# LAN.net
KiCad netlist of a schematic drawn in Altium Designer
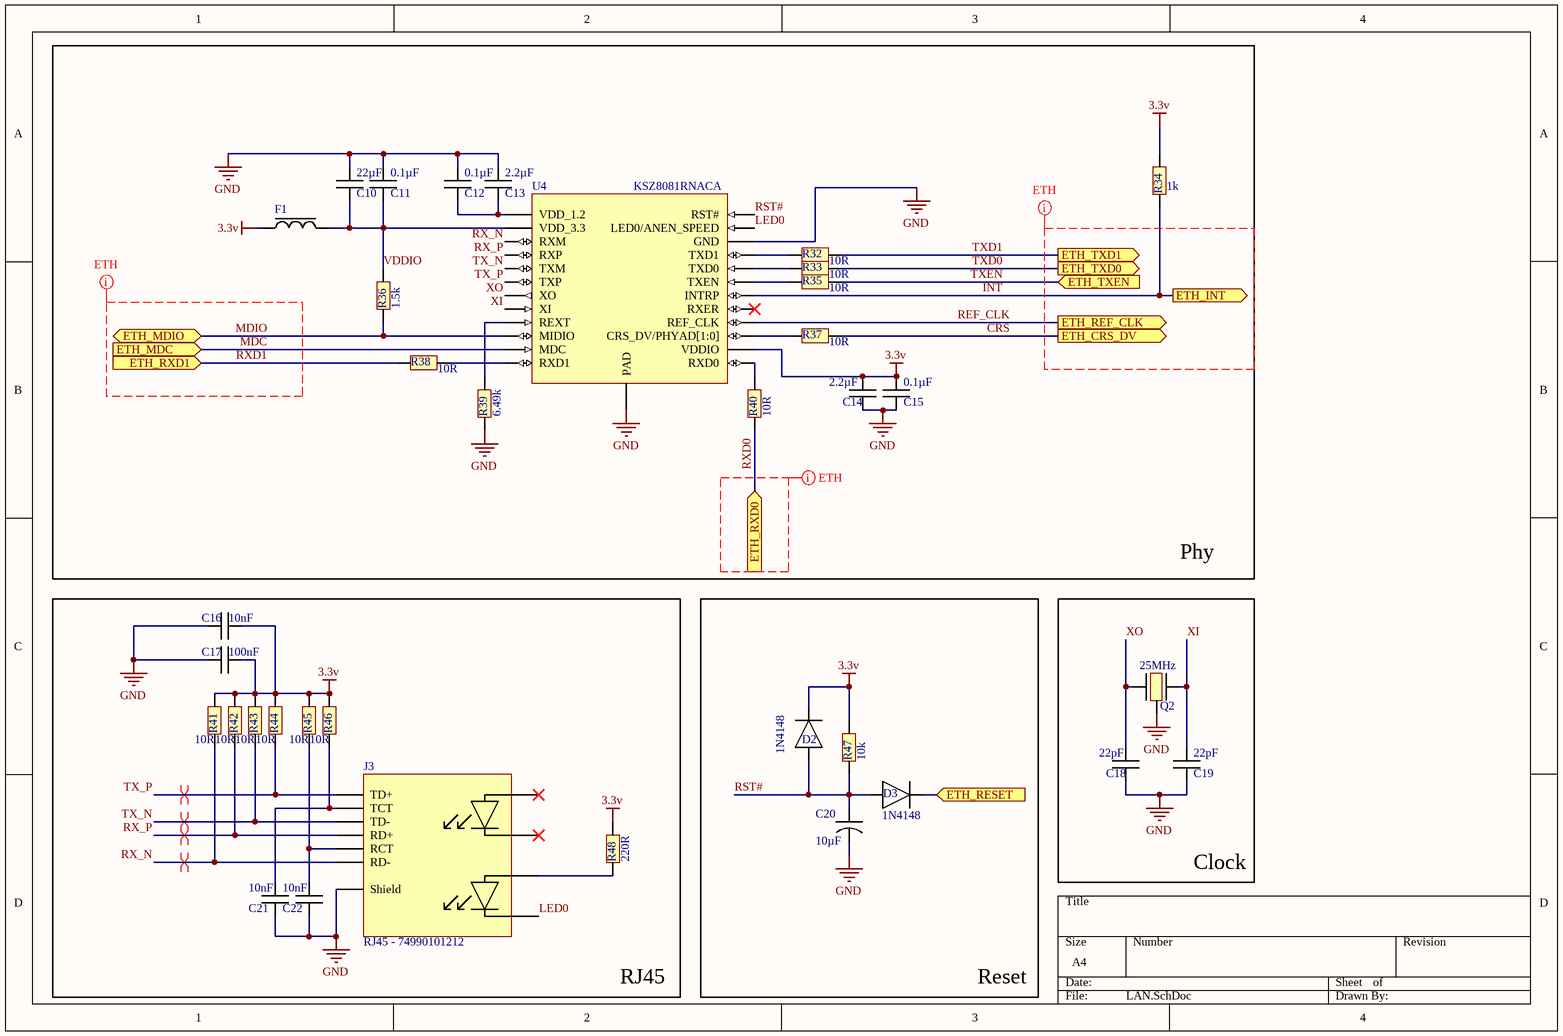
[diagram p0: LAN.SchDoc]

(export (version "E")
  (design (tool "Eeschema 10.0.6"))
  (components
    (comp (ref "C10") (value "22µF") (footprint "0603") (libsource (lib "Carte_design_SCHLib") (part "Capa")))
    (comp (ref "C11")
      (value "0.1µF")
      (footprint "0603")
      (libsource (lib "Carte_design_SCHLib") (part "Capa"))
    )
    (comp (ref "C12")
      (value "0.1µF")
      (footprint "0603")
      (libsource (lib "Carte_design_SCHLib") (part "Capa"))
    )
    (comp (ref "C13")
      (value "2.2µF")
      (footprint "0603")
      (libsource (lib "Carte_design_SCHLib") (part "Capa"))
    )
    (comp (ref "C14")
      (value "2.2µF")
      (footprint "0603")
      (libsource (lib "Carte_design_SCHLib") (part "Capa"))
    )
    (comp (ref "C15")
      (value "0.1µF")
      (footprint "0603")
      (libsource (lib "Carte_design_SCHLib") (part "Capa"))
    )
    (comp (ref "C16") (value "10nF") (footprint "0603") (libsource (lib "Carte_design_SCHLib") (part "Capa")))
    (comp (ref "C17")
      (value "100nF")
      (footprint "0603")
      (libsource (lib "Carte_design_SCHLib") (part "Capa"))
    )
    (comp (ref "C18") (value "22pF") (footprint "0603") (libsource (lib "Carte_design_SCHLib") (part "Capa")))
    (comp (ref "C19") (value "22pF") (footprint "0603") (libsource (lib "Carte_design_SCHLib") (part "Capa")))
    (comp (ref "C20")
      (value "10µF")
      (footprint "Capa_Radial_D4mm_H5.5mm")
      (fields (field (name "TOLERANCE") "20%"))
      (libsource (lib "Carte_design_SCHLib") (part "Capa_pola"))
    )
    (comp (ref "C21") (value "10nF") (footprint "0603") (libsource (lib "Carte_design_SCHLib") (part "Capa")))
    (comp (ref "C22") (value "10nF") (footprint "0603") (libsource (lib "Carte_design_SCHLib") (part "Capa")))
    (comp (ref "D2")
      (value "1N4148")
      (footprint "SOD123")
      (fields (field (name "VOLTAGE") "100V"))
      (libsource (lib "Carte_design_SCHLib") (part "1N4148"))
    )
    (comp (ref "D3")
      (value "1N4148")
      (footprint "SOD123")
      (fields (field (name "VOLTAGE") "100V"))
      (libsource (lib "Carte_design_SCHLib") (part "1N4148"))
    )
    (comp (ref "F1")
      (value "Ferrite")
      (footprint "0805_W1.25")
      (fields (field (name "TOLERANCE") "25%"))
      (libsource (lib "Carte_design_SCHLib") (part "Ferrite"))
    )
    (comp (ref "J3")
      (value "RJ45 - 74990101212")
      (footprint "RJ45")
      (libsource (lib "Carte_design_SCHLib") (part "RJ45"))
    )
    (comp (ref "Q2")
      (value "25MHz")
      (footprint "SMD_3225")
      (libsource (lib "Carte_design_SCHLib") (part "Quartz_25MHz"))
    )
    (comp (ref "R32") (value "10R") (footprint "0603") (libsource (lib "") (part "Resistance_1")))
    (comp (ref "R33") (value "10R") (footprint "0603") (libsource (lib "") (part "Resistance_1")))
    (comp (ref "R34")
      (value "1k")
      (footprint "0603")
      (libsource (lib "Carte_design_SCHLib") (part "Resistance"))
    )
    (comp (ref "R35") (value "10R") (footprint "0603") (libsource (lib "") (part "Resistance_1")))
    (comp (ref "R36") (value "1.5k") (footprint "0603") (libsource (lib "") (part "Resistance_2")))
    (comp (ref "R37") (value "10R") (footprint "0603") (libsource (lib "") (part "Resistance_1")))
    (comp (ref "R38") (value "10R") (footprint "0603") (libsource (lib "") (part "Resistance_3")))
    (comp (ref "R39") (value "6.49k") (footprint "0603") (libsource (lib "") (part "Resistance_2")))
    (comp (ref "R40")
      (value "10R")
      (footprint "0603")
      (libsource (lib "Carte_design_SCHLib") (part "Resistance"))
    )
    (comp (ref "R41") (value "10R") (footprint "0603") (libsource (lib "") (part "Resistance_2")))
    (comp (ref "R42") (value "10R") (footprint "0603") (libsource (lib "") (part "Resistance_2")))
    (comp (ref "R43") (value "10R") (footprint "0603") (libsource (lib "") (part "Resistance_2")))
    (comp (ref "R44") (value "10R") (footprint "0603") (libsource (lib "") (part "Resistance_2")))
    (comp (ref "R45") (value "10R") (footprint "0603") (libsource (lib "") (part "Resistance_2")))
    (comp (ref "R46") (value "10R") (footprint "0603") (libsource (lib "") (part "Resistance_2")))
    (comp (ref "R47") (value "10k") (footprint "0603") (libsource (lib "") (part "Resistance_2")))
    (comp (ref "R48") (value "220R") (footprint "0603") (libsource (lib "") (part "Resistance_2")))
    (comp (ref "U4")
      (value "KSZ8081RNACA")
      (footprint "QFN50P400X400X90_HS-25M")
      (description "IC TXRX ETHERNET 24QFN")
      (libsource (lib "Carte_design_SCHLib") (part "KSZ8081RNACA"))
    )
  )
  (nets
    (net (code "1") (name "/CRS") (class "Default")
      (node (ref "R37") (pin "1") (pinfunction "26_1") (pintype "passive"))
    )
    (net (code "2") (name "/ETH_RESET") (class "Default")
      (node (ref "D3") (pin "2") (pinfunction "31_2") (pintype "passive"))
    )
    (net (code "3") (name "/INT") (class "Default")
      (node (ref "R34") (pin "2") (pinfunction "27_2") (pintype "passive"))
      (node (ref "U4") (pin "18") (pinfunction "INTRP_18") (pintype "bidirectional"))
    )
    (net (code "4") (name "/LED0") (class "Default")
      (node (ref "J3") (pin "11") (pinfunction "11_11") (pintype "passive"))
      (node (ref "U4") (pin "23") (pinfunction "LED0/ANEN_SPEED_23") (pintype "input"))
    )
    (net (code "5") (name "/MDC") (class "Default")
      (node (ref "U4") (pin "11") (pinfunction "MDC_11") (pintype "input"))
    )
    (net (code "6") (name "/MDIO") (class "Default")
      (node (ref "R36") (pin "1") (pinfunction "26_1") (pintype "passive"))
      (node (ref "U4") (pin "10") (pinfunction "MIDIO_10") (pintype "bidirectional"))
    )
    (net (code "7") (name "/REF_CLK") (class "Default")
      (node (ref "U4") (pin "16") (pinfunction "REF_CLK_16") (pintype "bidirectional"))
    )
    (net (code "8") (name "/RST#") (class "Default")
      (node (ref "C20") (pin "1") (pinfunction "28_1") (pintype "passive"))
      (node (ref "D2") (pin "1") (pinfunction "30_1") (pintype "passive"))
      (node (ref "D3") (pin "1") (pinfunction "30_1") (pintype "passive"))
      (node (ref "R47") (pin "1") (pinfunction "26_1") (pintype "passive"))
      (node (ref "U4") (pin "24") (pinfunction "RST#_24") (pintype "input"))
    )
    (net (code "9") (name "/RXD0") (class "Default")
      (node (ref "R40") (pin "2") (pinfunction "27_2") (pintype "passive"))
    )
    (net (code "10") (name "/RXD1") (class "Default")
      (node (ref "R38") (pin "1") (pinfunction "26_1") (pintype "passive"))
    )
    (net (code "11") (name "/RX_N") (class "Default")
      (node (ref "J3") (pin "6") (pinfunction "RD-_6") (pintype "passive"))
      (node (ref "R41") (pin "1") (pinfunction "26_1") (pintype "passive"))
      (node (ref "U4") (pin "3") (pinfunction "RXM_3") (pintype "bidirectional"))
    )
    (net (code "12") (name "/RX_P") (class "Default")
      (node (ref "J3") (pin "4") (pinfunction "RD+_4") (pintype "passive"))
      (node (ref "R42") (pin "1") (pinfunction "26_1") (pintype "passive"))
      (node (ref "U4") (pin "4") (pinfunction "RXP_4") (pintype "bidirectional"))
    )
    (net (code "13") (name "/TXD0") (class "Default")
      (node (ref "R33") (pin "1") (pinfunction "26_1") (pintype "passive"))
    )
    (net (code "14") (name "/TXD1") (class "Default")
      (node (ref "R32") (pin "1") (pinfunction "26_1") (pintype "passive"))
    )
    (net (code "15") (name "/TXEN") (class "Default")
      (node (ref "R35") (pin "1") (pinfunction "26_1") (pintype "passive"))
    )
    (net (code "16") (name "/TX_N") (class "Default")
      (node (ref "J3") (pin "3") (pinfunction "TD-_3") (pintype "passive"))
      (node (ref "R43") (pin "1") (pinfunction "26_1") (pintype "passive"))
      (node (ref "U4") (pin "5") (pinfunction "TXM_5") (pintype "bidirectional"))
    )
    (net (code "17") (name "/TX_P") (class "Default")
      (node (ref "J3") (pin "1") (pinfunction "TD+_1") (pintype "passive"))
      (node (ref "R44") (pin "1") (pinfunction "26_1") (pintype "passive"))
      (node (ref "U4") (pin "6") (pinfunction "TXP_6") (pintype "bidirectional"))
    )
    (net (code "18") (name "/VDDIO") (class "Default")
      (node (ref "C10") (pin "1") (pinfunction "29_1") (pintype "passive"))
      (node (ref "C11") (pin "1") (pinfunction "29_1") (pintype "passive"))
      (node (ref "F1") (pin "2") (pinfunction "18_2") (pintype "passive"))
      (node (ref "R36") (pin "2") (pinfunction "27_2") (pintype "passive"))
      (node (ref "U4") (pin "2") (pinfunction "VDD_3.3_2") (pintype "power_in"))
    )
    (net (code "19") (name "/XI") (class "Default")
      (node (ref "C19") (pin "2") (pinfunction "28_2") (pintype "passive"))
      (node (ref "Q2") (pin "2") (pinfunction "16_2") (pintype "passive"))
      (node (ref "U4") (pin "8") (pinfunction "XI_8") (pintype "input"))
    )
    (net (code "20") (name "/XO") (class "Default")
      (node (ref "C18") (pin "2") (pinfunction "28_2") (pintype "passive"))
      (node (ref "Q2") (pin "1") (pinfunction "15_1") (pintype "passive"))
      (node (ref "U4") (pin "7") (pinfunction "XO_7") (pintype "output"))
    )
    (net (code "21") (name "3.3v") (class "Default")
      (node (ref "C14") (pin "2") (pinfunction "28_2") (pintype "passive"))
      (node (ref "C15") (pin "2") (pinfunction "28_2") (pintype "passive"))
      (node (ref "C16") (pin "2") (pinfunction "28_2") (pintype "passive"))
      (node (ref "C17") (pin "2") (pinfunction "28_2") (pintype "passive"))
      (node (ref "D2") (pin "2") (pinfunction "31_2") (pintype "passive"))
      (node (ref "F1") (pin "1") (pinfunction "17_1") (pintype "passive"))
      (node (ref "R34") (pin "1") (pinfunction "26_1") (pintype "passive"))
      (node (ref "R41") (pin "2") (pinfunction "27_2") (pintype "passive"))
      (node (ref "R42") (pin "2") (pinfunction "27_2") (pintype "passive"))
      (node (ref "R43") (pin "2") (pinfunction "27_2") (pintype "passive"))
      (node (ref "R44") (pin "2") (pinfunction "27_2") (pintype "passive"))
      (node (ref "R45") (pin "2") (pinfunction "27_2") (pintype "passive"))
      (node (ref "R46") (pin "2") (pinfunction "27_2") (pintype "passive"))
      (node (ref "R47") (pin "2") (pinfunction "27_2") (pintype "passive"))
      (node (ref "R48") (pin "2") (pinfunction "27_2") (pintype "passive"))
      (node (ref "U4") (pin "14") (pinfunction "VDDIO_14") (pintype "power_in"))
    )
    (net (code "22") (name "GND") (class "Default")
      (node (ref "C10") (pin "2") (pinfunction "28_2") (pintype "passive"))
      (node (ref "C11") (pin "2") (pinfunction "28_2") (pintype "passive"))
      (node (ref "C12") (pin "2") (pinfunction "28_2") (pintype "passive"))
      (node (ref "C13") (pin "2") (pinfunction "28_2") (pintype "passive"))
      (node (ref "C14") (pin "1") (pinfunction "29_1") (pintype "passive"))
      (node (ref "C15") (pin "1") (pinfunction "29_1") (pintype "passive"))
      (node (ref "C16") (pin "1") (pinfunction "29_1") (pintype "passive"))
      (node (ref "C17") (pin "1") (pinfunction "29_1") (pintype "passive"))
      (node (ref "C18") (pin "1") (pinfunction "29_1") (pintype "passive"))
      (node (ref "C19") (pin "1") (pinfunction "29_1") (pintype "passive"))
      (node (ref "C20") (pin "2") (pinfunction "28_2") (pintype "passive"))
      (node (ref "C21") (pin "1") (pinfunction "29_1") (pintype "passive"))
      (node (ref "C22") (pin "1") (pinfunction "29_1") (pintype "passive"))
      (node (ref "J3") (pin "8") (pinfunction "Shield_8") (pintype "passive"))
      (node (ref "Q2") (pin "3") (pinfunction "3_3") (pintype "passive"))
      (node (ref "R39") (pin "1") (pinfunction "26_1") (pintype "passive"))
      (node (ref "U4") (pin "22") (pinfunction "GND_22") (pintype "power_in"))
      (node (ref "U4") (pin "25") (pinfunction "PAD_25") (pintype "power_in"))
    )
    (net (code "23") (name "Net-(C12-29)") (class "Default")
      (node (ref "C12") (pin "1") (pinfunction "29_1") (pintype "passive"))
      (node (ref "C13") (pin "1") (pinfunction "29_1") (pintype "passive"))
      (node (ref "U4") (pin "1") (pinfunction "VDD_1.2_1") (pintype "power_in"))
    )
    (net (code "24") (name "Net-(C21-28)") (class "Default")
      (node (ref "C21") (pin "2") (pinfunction "28_2") (pintype "passive"))
      (node (ref "J3") (pin "2") (pinfunction "TCT_2") (pintype "passive"))
      (node (ref "R46") (pin "1") (pinfunction "26_1") (pintype "passive"))
    )
    (net (code "25") (name "Net-(C22-28)") (class "Default")
      (node (ref "C22") (pin "2") (pinfunction "28_2") (pintype "passive"))
      (node (ref "J3") (pin "5") (pinfunction "RCT_5") (pintype "passive"))
      (node (ref "R45") (pin "1") (pinfunction "26_1") (pintype "passive"))
    )
    (net (code "26") (name "Net-(R32-27)") (class "Default")
      (node (ref "R32") (pin "2") (pinfunction "27_2") (pintype "passive"))
      (node (ref "U4") (pin "21") (pinfunction "TXD1_21") (pintype "bidirectional"))
    )
    (net (code "27") (name "Net-(R33-27)") (class "Default")
      (node (ref "R33") (pin "2") (pinfunction "27_2") (pintype "passive"))
      (node (ref "U4") (pin "20") (pinfunction "TXD0_20") (pintype "input"))
    )
    (net (code "28") (name "Net-(R35-27)") (class "Default")
      (node (ref "R35") (pin "2") (pinfunction "27_2") (pintype "passive"))
      (node (ref "U4") (pin "19") (pinfunction "TXEN_19") (pintype "input"))
    )
    (net (code "29") (name "Net-(R37-27)") (class "Default")
      (node (ref "R37") (pin "2") (pinfunction "27_2") (pintype "passive"))
      (node (ref "U4") (pin "15") (pinfunction "CRS_DV/PHYAD[1:0]_15") (pintype "bidirectional"))
    )
    (net (code "30") (name "Net-(R38-27)") (class "Default")
      (node (ref "R38") (pin "2") (pinfunction "27_2") (pintype "passive"))
      (node (ref "U4") (pin "12") (pinfunction "RXD1_12") (pintype "bidirectional"))
    )
    (net (code "31") (name "Net-(R39-27)") (class "Default")
      (node (ref "R39") (pin "2") (pinfunction "27_2") (pintype "passive"))
      (node (ref "U4") (pin "9") (pinfunction "REXT_9") (pintype "input"))
    )
    (net (code "32") (name "Net-(R40-26)") (class "Default")
      (node (ref "R40") (pin "1") (pinfunction "26_1") (pintype "passive"))
      (node (ref "U4") (pin "13") (pinfunction "RXD0_13") (pintype "bidirectional"))
    )
    (net (code "33") (name "Net-(R48-26)") (class "Default")
      (node (ref "J3") (pin "12") (pinfunction "12_12") (pintype "passive"))
      (node (ref "R48") (pin "1") (pinfunction "26_1") (pintype "passive"))
    )
    (net (code "34") (name "unconnected-(J3-11-Pad10)") (class "Default")
      (node (ref "J3") (pin "10") (pinfunction "11_10") (pintype "passive+no_connect"))
    )
    (net (code "35") (name "unconnected-(J3-Pad9)") (class "Default")
      (node (ref "J3") (pin "9") (pinfunction "9_9") (pintype "passive+no_connect"))
    )
    (net (code "36") (name "unconnected-(U4-RXER-Pad17)") (class "Default")
      (node (ref "U4") (pin "17") (pinfunction "RXER_17") (pintype "bidirectional+no_connect"))
    )
  )
)
